# 0151_DC_JACK_RTC_COIN.net
KiCad netlist of a schematic drawn in Altium Designer
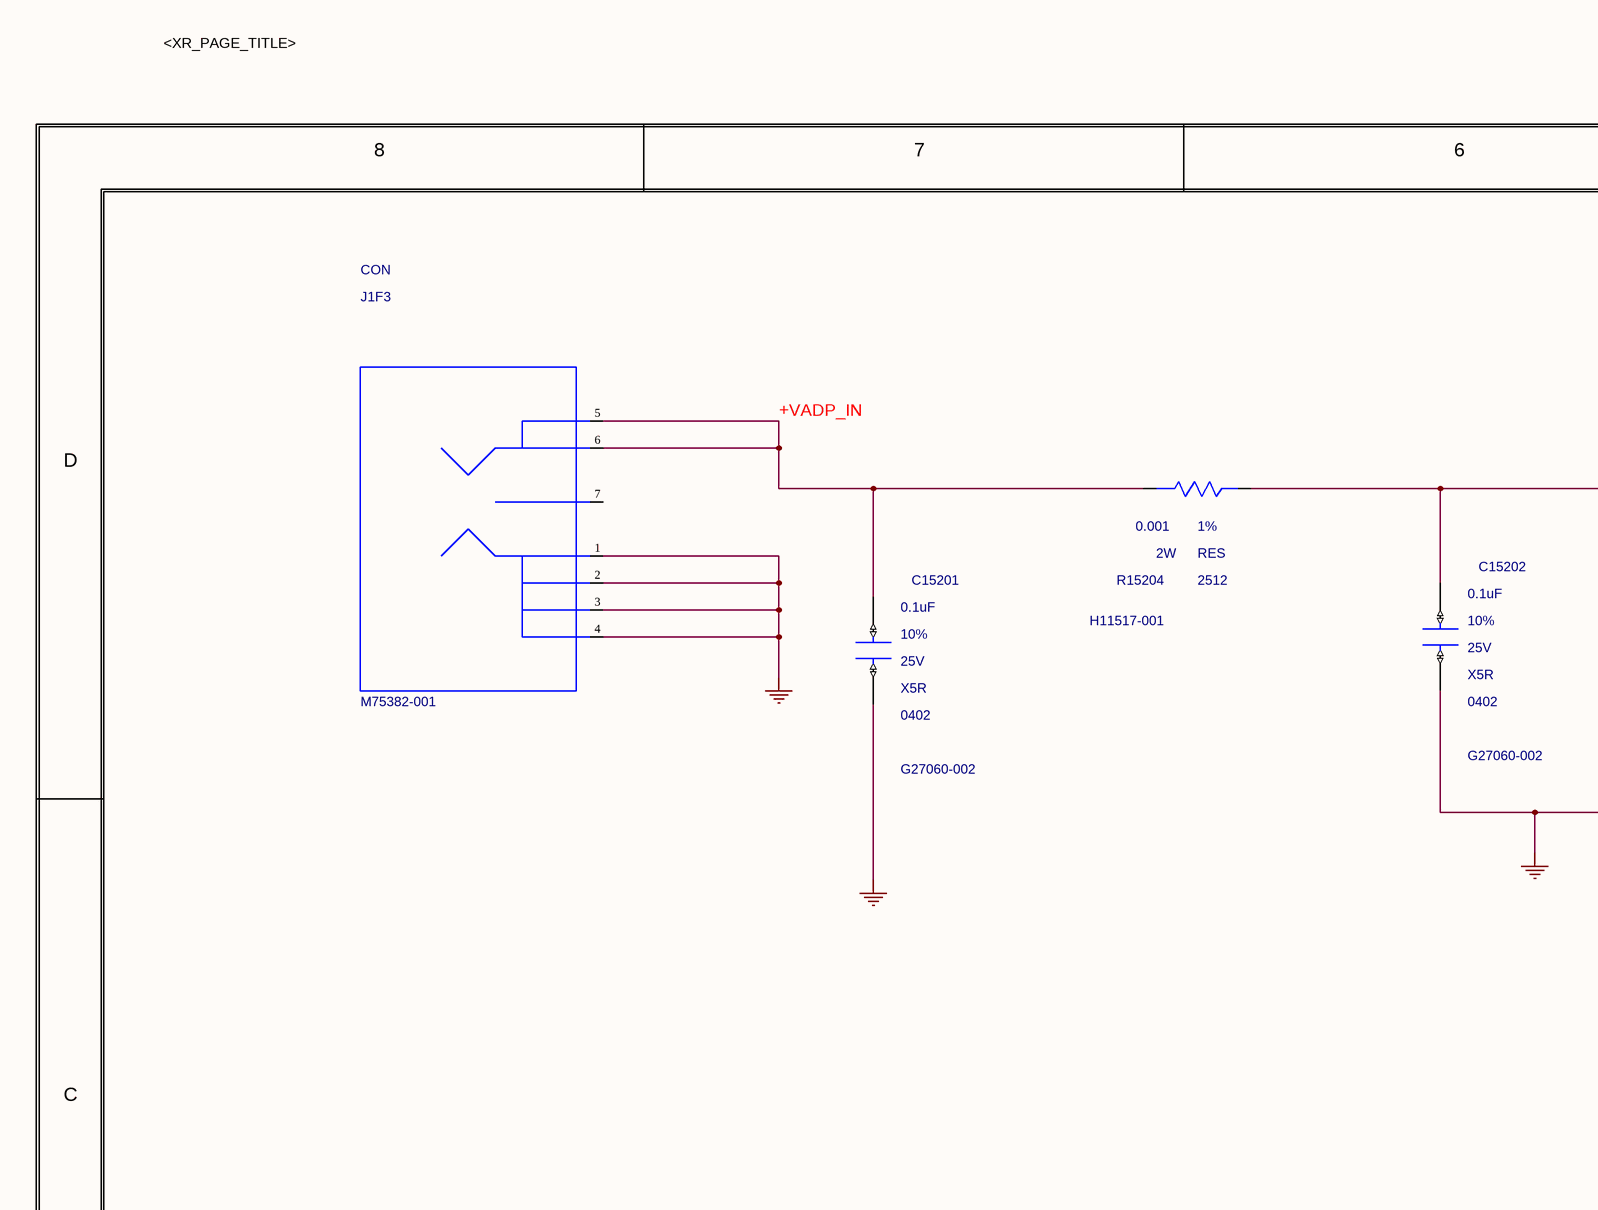
[diagram p0: 0151_DC JACK & RTC COIN.SchDoc, top left]
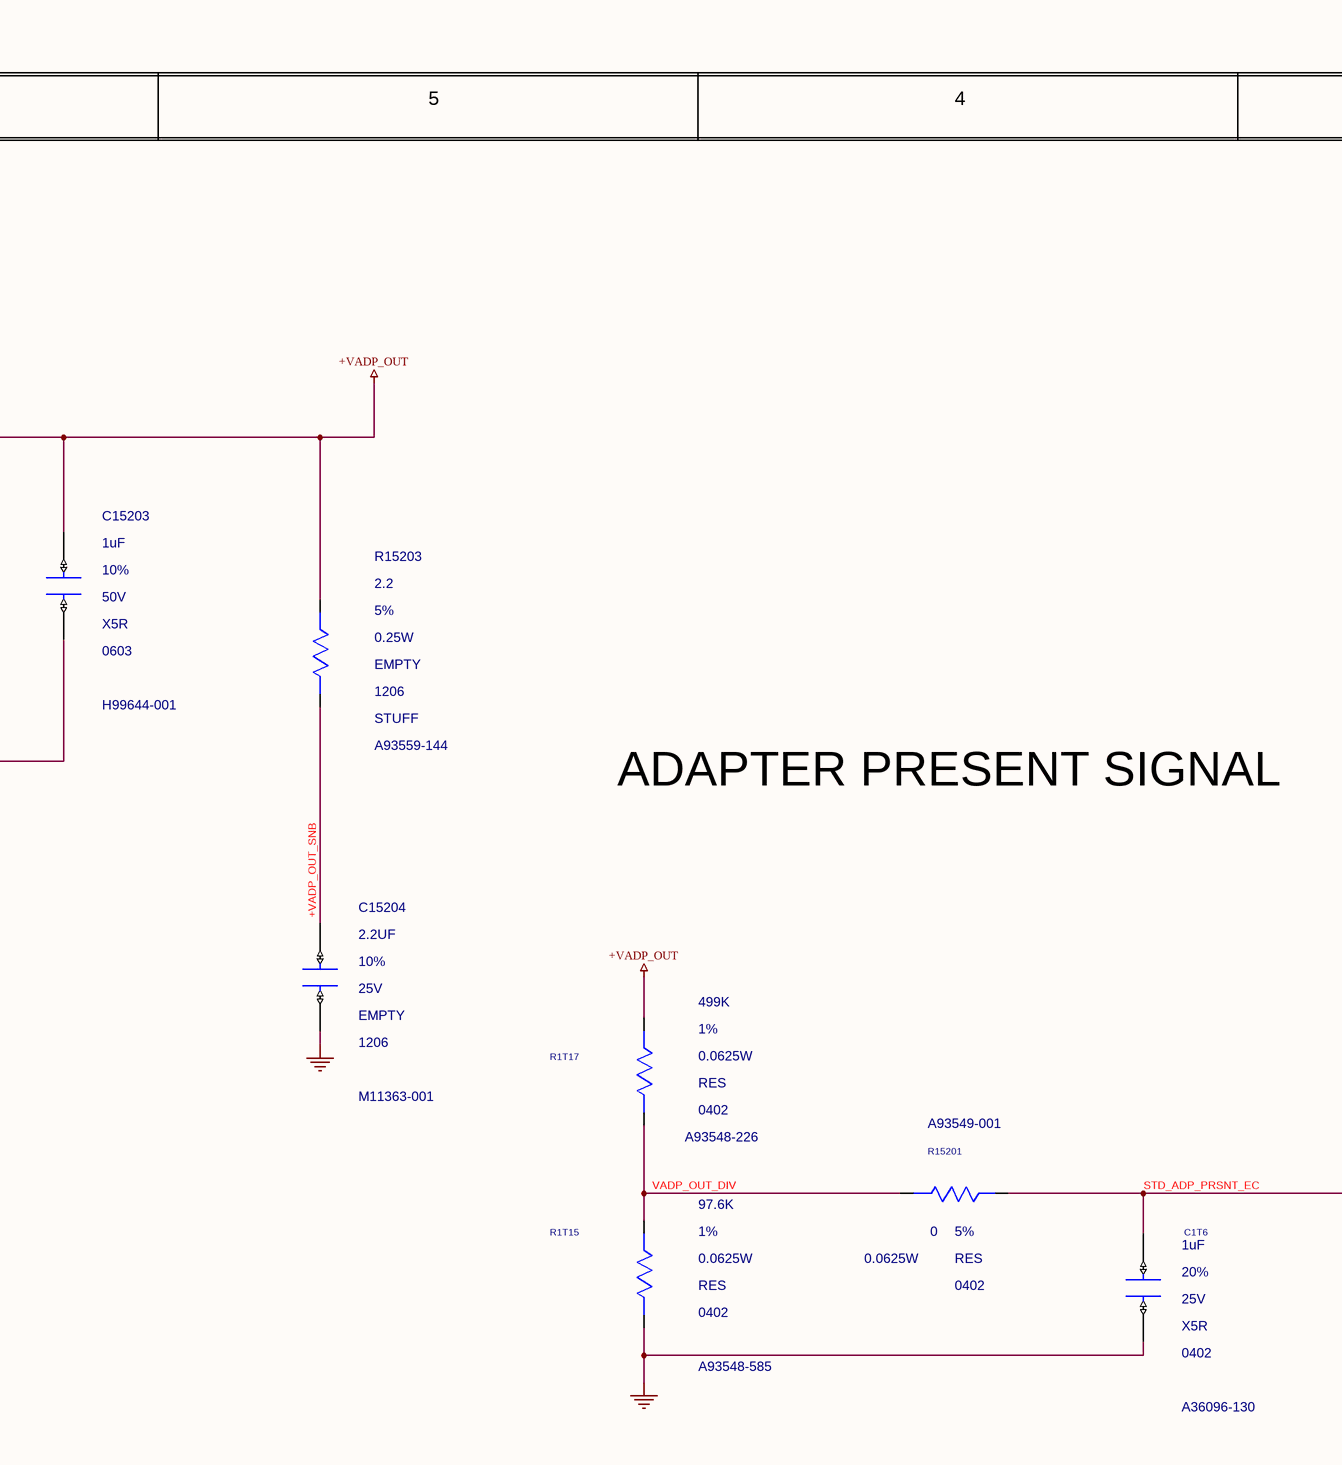
[diagram p1: 0151_DC JACK & RTC COIN.SchDoc, top middle]
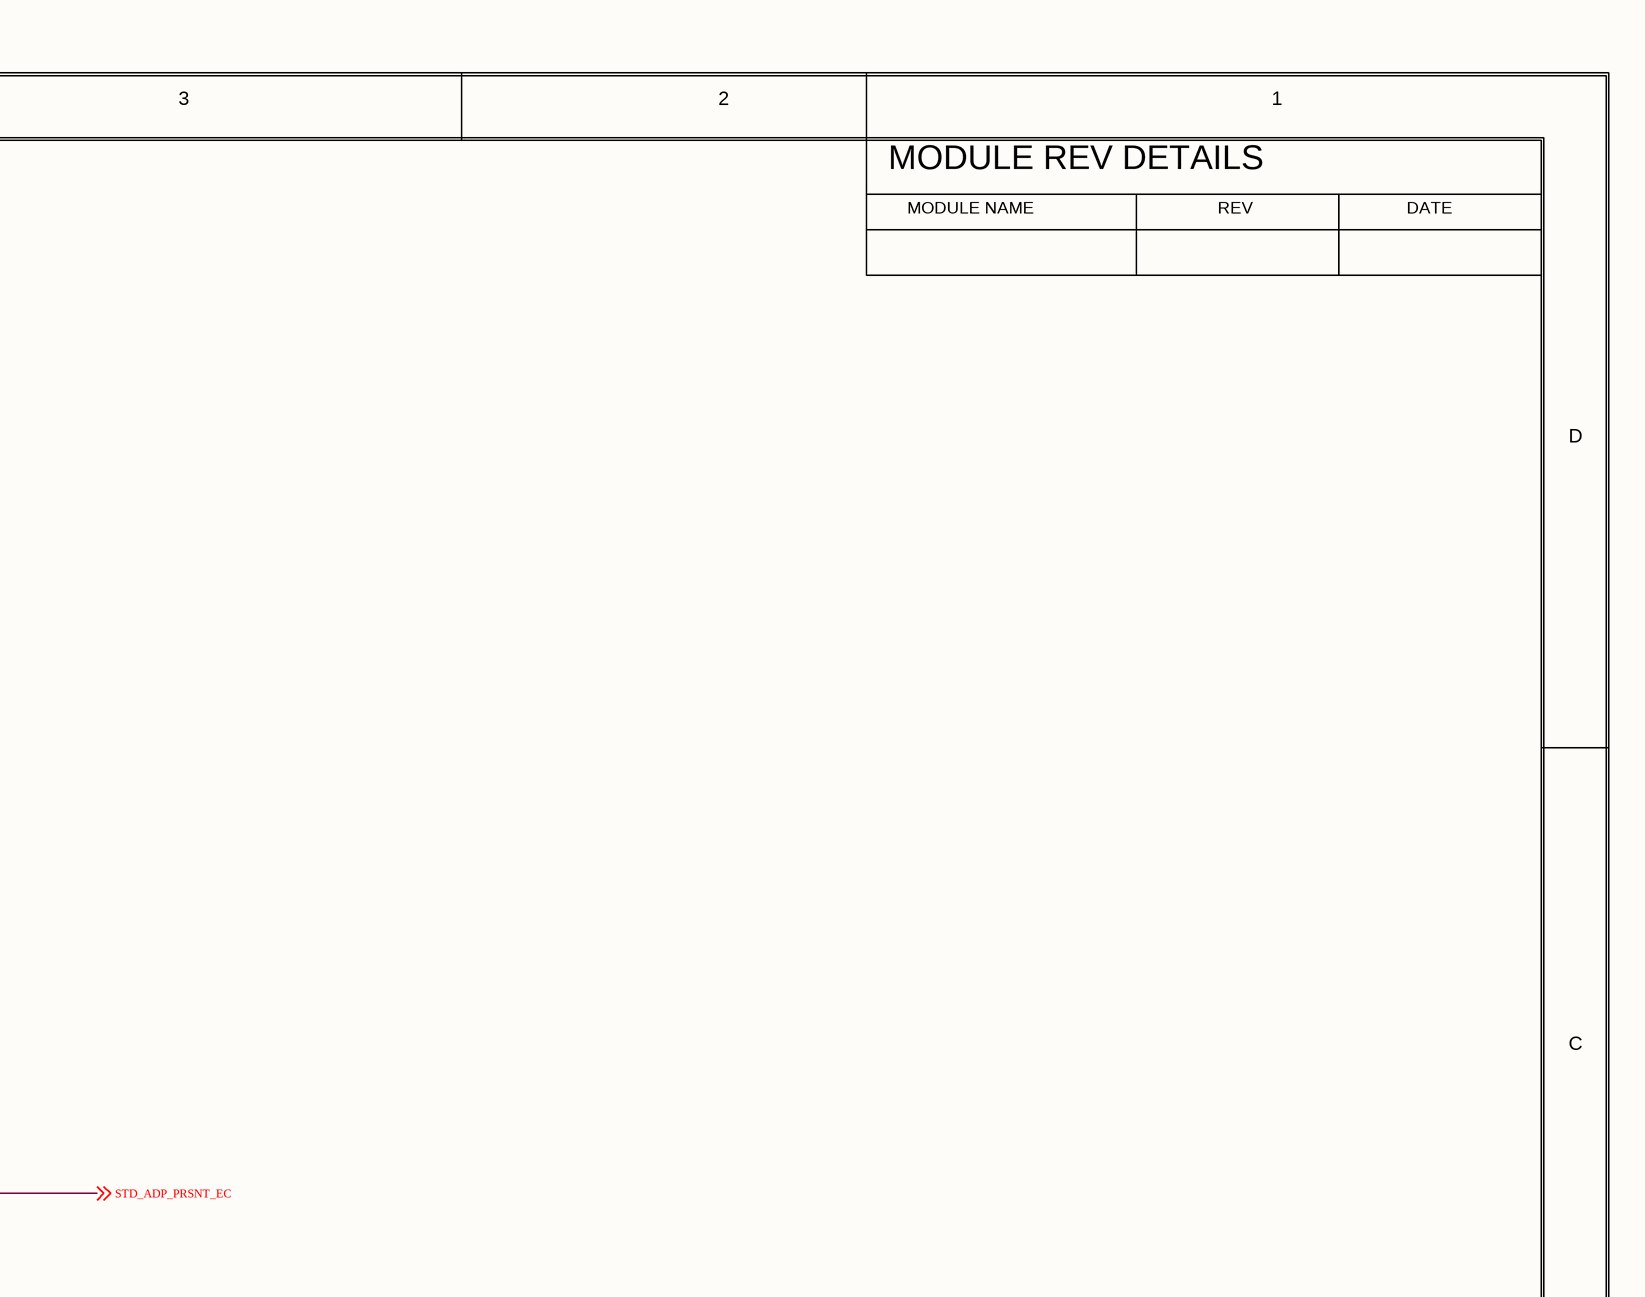
[diagram p2: 0151_DC JACK & RTC COIN.SchDoc, top right]
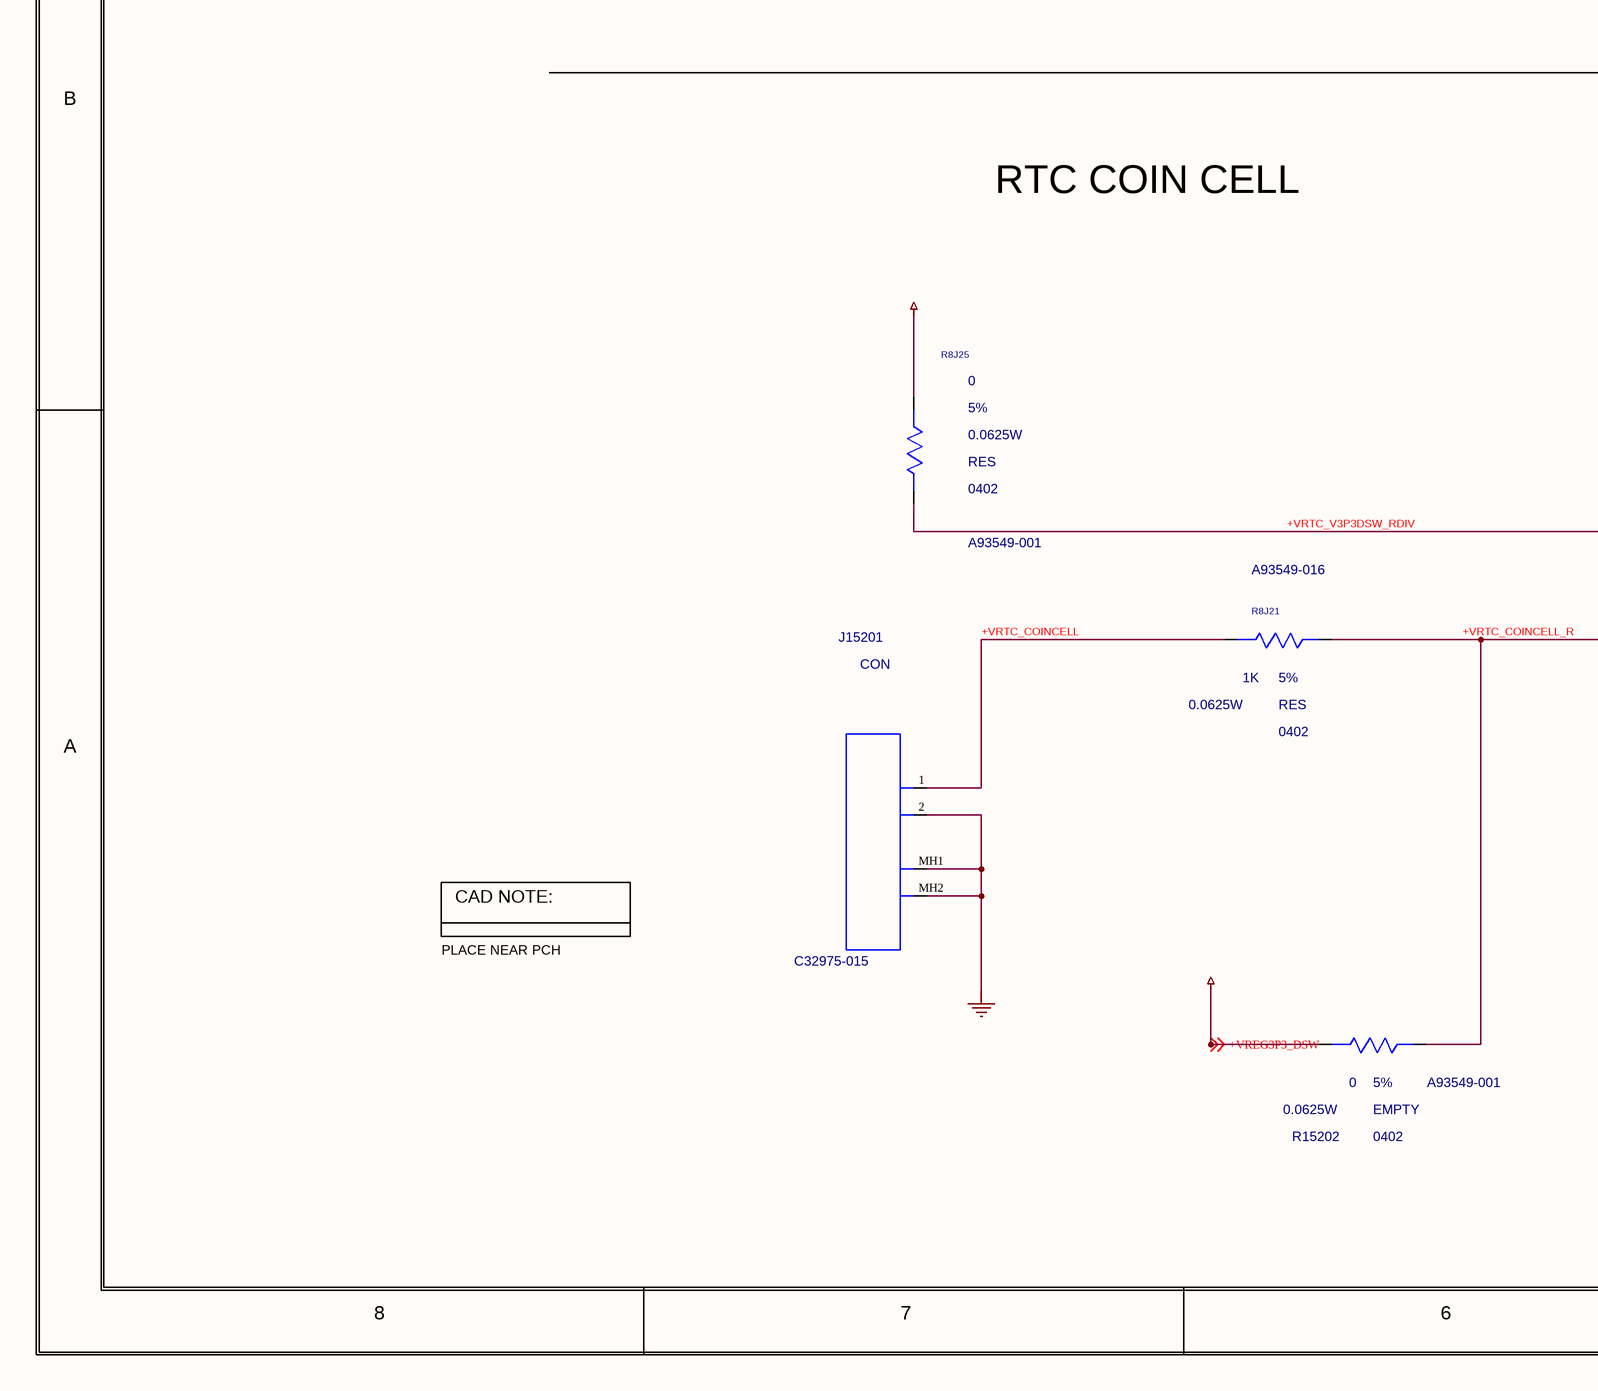
[diagram p3: 0151_DC JACK & RTC COIN.SchDoc, bottom left]
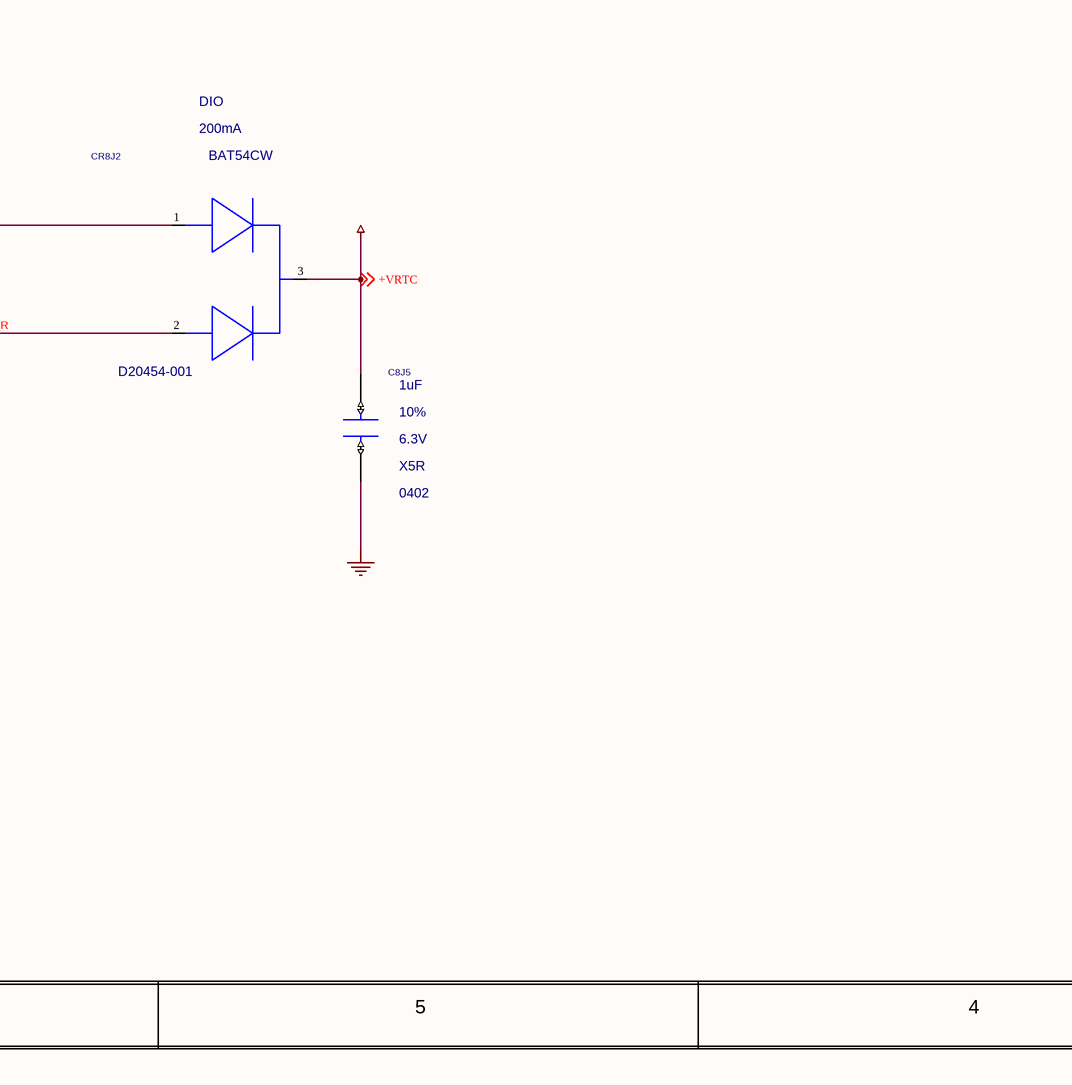
[diagram p4: 0151_DC JACK & RTC COIN.SchDoc, bottom middle]
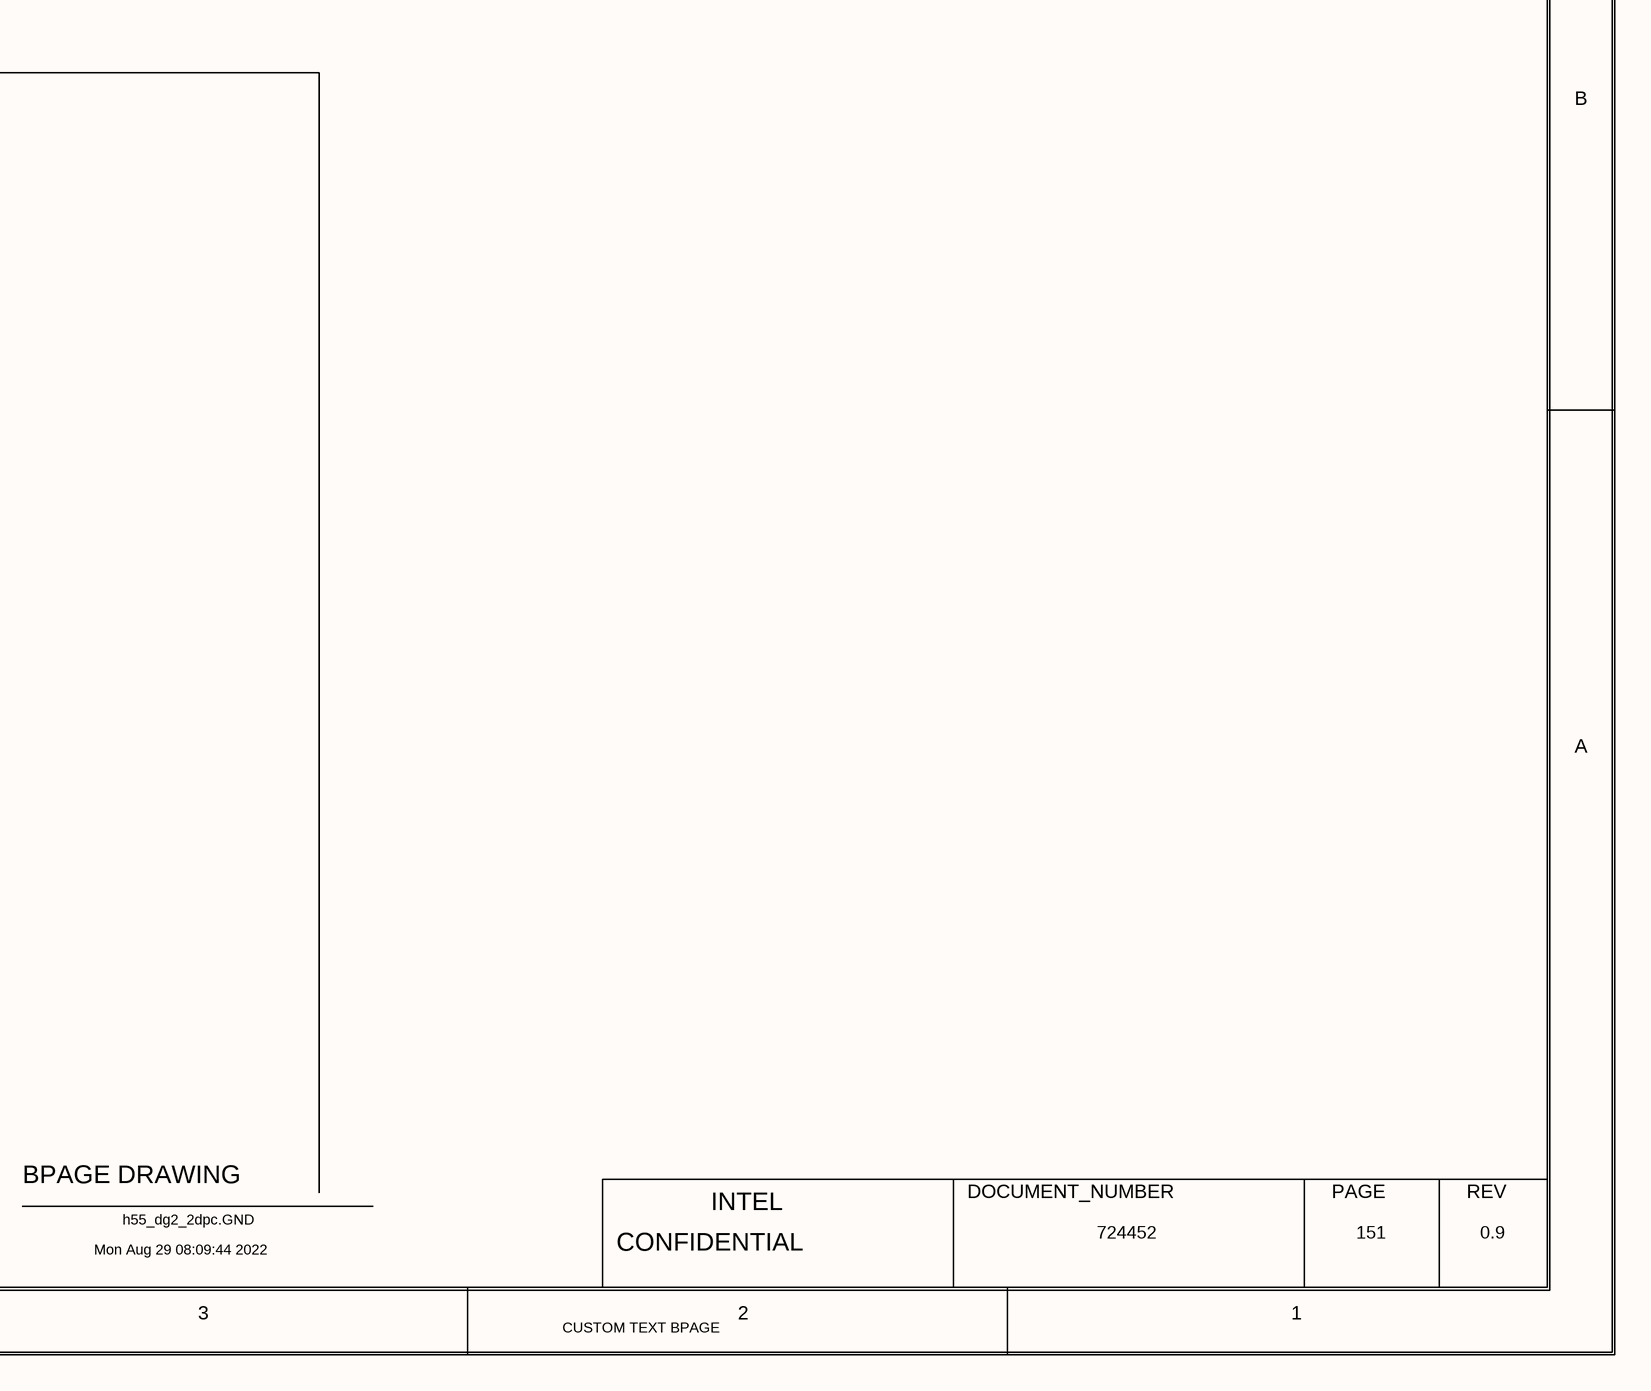
[diagram p5: 0151_DC JACK & RTC COIN.SchDoc, bottom right]

(export (version "E")
  (design (tool "Eeschema 10.0.6"))
  (components
    (comp (ref "C1T6")
      (value "1uF")
      (footprint "CTK0_SM0402_1050X550_MA")
      (fields
        (field (name "MATERIAL") "X5R")
        (field (name "PACK_TYPE") "0402")
        (field (name "PART_NUMBER") "A36096-130")
        (field (name "TOLERANCE") "20%")
        (field (name "VOLTAGE") "25V")
      )
      (libsource (lib "*") (part "C_CAP"))
    )
    (comp (ref "C8J5")
      (value "1uF")
      (footprint "CTK2_SM0402_1050X550_MA")
      (fields
        (field (name "MATERIAL") "X5R")
        (field (name "PACK_TYPE") "0402")
        (field (name "PART_NUMBER") "A36096-027")
        (field (name "TOLERANCE") "10%")
        (field (name "VOLTAGE") "6.3V")
      )
      (libsource (lib "*") (part "C_CAP"))
    )
    (comp (ref "C15201")
      (value "0.1uF")
      (footprint "CTK2_SM0402_1050X550_MA")
      (fields
        (field (name "MATERIAL") "X5R")
        (field (name "PACK_TYPE") "0402")
        (field (name "PART_NUMBER") "G27060-002")
        (field (name "TOLERANCE") "10%")
        (field (name "VOLTAGE") "25V")
      )
      (libsource (lib "*") (part "C_CAP"))
    )
    (comp (ref "C15202")
      (value "0.1uF")
      (footprint "CTK2_SM0402_1050X550_MA")
      (fields
        (field (name "MATERIAL") "X5R")
        (field (name "PACK_TYPE") "0402")
        (field (name "PART_NUMBER") "G27060-002")
        (field (name "TOLERANCE") "10%")
        (field (name "VOLTAGE") "25V")
      )
      (libsource (lib "*") (part "C_CAP"))
    )
    (comp (ref "C15203")
      (value "1uF")
      (footprint "CTK0_SM0603_1750X950_MA")
      (fields
        (field (name "MATERIAL") "X5R")
        (field (name "PACK_TYPE") "0603")
        (field (name "PART_NUMBER") "H99644-001")
        (field (name "TOLERANCE") "10%")
        (field (name "VOLTAGE") "50V")
      )
      (libsource (lib "*") (part "C_CAP"))
    )
    (comp (ref "C15204")
      (value "2.2UF")
      (footprint "CTK2_SM1206_3400X1800_MB")
      (fields
        (field (name "MATERIAL") "EMPTY")
        (field (name "PACK_TYPE") "1206")
        (field (name "PART_NUMBER") "M11363-001")
        (field (name "TOLERANCE") "10%")
        (field (name "VOLTAGE") "25V")
      )
      (libsource (lib "*") (part "C_CAP"))
    )
    (comp (ref "CR8J2")
      (value "BAT54CW")
      (footprint "CTK2_SOT323_1350X2200_650_MB")
      (fields
        (field (name "CURRENT") "200mA")
        (field (name "MATERIAL") "DIO")
        (field (name "PART_NUMBER") "D20454-001")
      )
      (libsource (lib "*") (part "C_BAT54C"))
    )
    (comp (ref "J1F3")
      (value "C_PWR_JACK_7P")
      (footprint "CPWR_JACK_MIDJR_7P_1530_MA_PIP_VR")
      (fields (field (name "MATERIAL") "CON") (field (name "PART_NUMBER") "M75382-001"))
      (libsource (lib "*") (part "C_PWR_JACK_7P"))
    )
    (comp (ref "J15201")
      (value "C_B2B_1X2_2EM")
      (footprint "CTK0_B2B_SPR_1X2_2EM_1250_MA_VR")
      (fields (field (name "MATERIAL") "CON") (field (name "PART_NUMBER") "C32975-015"))
      (libsource (lib "*") (part "C_B2B_1X2_2EM"))
    )
    (comp (ref "R1T15")
      (value "97.6K")
      (footprint "CTK0_SM0402_1100X550_MA")
      (fields
        (field (name "MATERIAL") "RES")
        (field (name "PACK_TYPE") "0402")
        (field (name "PART_NUMBER") "A93548-585")
        (field (name "TOLERANCE") "1%")
        (field (name "WATTAGE") "0.0625W")
      )
      (libsource (lib "*") (part "C_RES"))
    )
    (comp (ref "R1T17")
      (value "499K")
      (footprint "CTK0_SM0402_1100X550_MA")
      (fields
        (field (name "MATERIAL") "RES")
        (field (name "PACK_TYPE") "0402")
        (field (name "PART_NUMBER") "A93548-226")
        (field (name "TOLERANCE") "1%")
        (field (name "WATTAGE") "0.0625W")
      )
      (libsource (lib "*") (part "C_RES"))
    )
    (comp (ref "R8J21")
      (value "1K")
      (footprint "CTK2_SM0402_1050X550_MA")
      (fields
        (field (name "MATERIAL") "RES")
        (field (name "PACK_TYPE") "0402")
        (field (name "PART_NUMBER") "A93549-016")
        (field (name "TOLERANCE") "5%")
        (field (name "WATTAGE") "0.0625W")
      )
      (libsource (lib "*") (part "C_RES#1"))
    )
    (comp (ref "R8J25")
      (value "0")
      (footprint "CTK0_SM0402_1100X550_MA")
      (fields
        (field (name "MATERIAL") "RES")
        (field (name "PACK_TYPE") "0402")
        (field (name "PART_NUMBER") "A93549-001")
        (field (name "TOLERANCE") "5%")
        (field (name "WATTAGE") "0.0625W")
      )
      (libsource (lib "*") (part "C_RES"))
    )
    (comp (ref "R15201")
      (value "0")
      (footprint "CTK0_SM0402_1100X550_MA")
      (fields
        (field (name "MATERIAL") "RES")
        (field (name "PACK_TYPE") "0402")
        (field (name "PART_NUMBER") "A93549-001")
        (field (name "TOLERANCE") "5%")
        (field (name "WATTAGE") "0.0625W")
      )
      (libsource (lib "*") (part "C_RES#1"))
    )
    (comp (ref "R15202")
      (value "0")
      (footprint "CTK0_SM0402_1100X550_MA")
      (fields
        (field (name "MATERIAL") "EMPTY")
        (field (name "PACK_TYPE") "0402")
        (field (name "PART_NUMBER") "A93549-001")
        (field (name "TOLERANCE") "5%")
        (field (name "WATTAGE") "0.0625W")
      )
      (libsource (lib "*") (part "C_RES#1"))
    )
    (comp (ref "R15203")
      (value "2.2")
      (footprint "TK0_SM1206_3400X1800_ML")
      (fields
        (field (name "BOM_USE") "STUFF")
        (field (name "MATERIAL") "EMPTY")
        (field (name "PACK_TYPE") "1206")
        (field (name "PART_NUMBER") "A93559-144")
        (field (name "TOLERANCE") "5%")
        (field (name "WATTAGE") "0.25W")
      )
      (libsource (lib "*") (part "RES_2"))
    )
    (comp (ref "R15204")
      (value "0.001")
      (footprint "CTK2_SM2512_6604X3434_MA")
      (fields
        (field (name "MATERIAL") "RES")
        (field (name "PACK_TYPE") "2512")
        (field (name "PART_NUMBER") "H11517-001")
        (field (name "TOLERANCE") "1%")
        (field (name "WATTAGE") "2W")
      )
      (libsource (lib "*") (part "C_RES#1"))
    )
  )
  (nets
    (net (code "1") (name "+V3P3DSW") (class "Default")
      (node (ref "R8J25") (pin "1") (pinfunction "A_1") (pintype "bidirectional"))
    )
    (net (code "2") (name "+VADP_OUT") (class "Default")
      (node (ref "C15202") (pin "1") (pinfunction "A_1") (pintype "bidirectional"))
      (node (ref "C15203") (pin "1") (pinfunction "A_1") (pintype "bidirectional"))
      (node (ref "R15203") (pin "1") (pinfunction "A_1") (pintype "bidirectional"))
      (node (ref "R15204") (pin "2") (pinfunction "B_2") (pintype "bidirectional"))
      (node (ref "R1T17") (pin "1") (pinfunction "A_1") (pintype "bidirectional"))
    )
    (net (code "3") (name "+VREG3P3_DSW") (class "Default")
      (node (ref "R15202") (pin "1") (pinfunction "A_1") (pintype "bidirectional"))
    )
    (net (code "4") (name "+VRTC") (class "Default")
      (node (ref "C8J5") (pin "1") (pinfunction "A_1") (pintype "bidirectional"))
      (node (ref "CR8J2") (pin "3") (pinfunction "C_3") (pintype "bidirectional"))
    )
    (net (code "5") (name "/+VADP_IN") (class "Default")
      (node (ref "C15201") (pin "1") (pinfunction "A_1") (pintype "bidirectional"))
      (node (ref "J1F3") (pin "5") (pinfunction "SPRING_P_1_5") (pintype "bidirectional"))
      (node (ref "J1F3") (pin "6") (pinfunction "SPRING_P_2_6") (pintype "bidirectional"))
      (node (ref "R15204") (pin "1") (pinfunction "A_1") (pintype "bidirectional"))
    )
    (net (code "6") (name "/+VADP_OUT_SNB") (class "Default")
      (node (ref "C15204") (pin "1") (pinfunction "A_1") (pintype "bidirectional"))
      (node (ref "R15203") (pin "2") (pinfunction "B_2") (pintype "bidirectional"))
    )
    (net (code "7") (name "/+VRTC_COINCELL") (class "Default")
      (node (ref "J15201") (pin "1") (pinfunction "IO1_1") (pintype "bidirectional"))
      (node (ref "R8J21") (pin "1") (pinfunction "A_1") (pintype "bidirectional"))
    )
    (net (code "8") (name "/+VRTC_COINCELL_R") (class "Default")
      (node (ref "CR8J2") (pin "2") (pinfunction "A2_2") (pintype "bidirectional"))
      (node (ref "R15202") (pin "2") (pinfunction "B_2") (pintype "bidirectional"))
      (node (ref "R8J21") (pin "2") (pinfunction "B_2") (pintype "bidirectional"))
    )
    (net (code "9") (name "/+VRTC_V3P3DSW_RDIV") (class "Default")
      (node (ref "CR8J2") (pin "1") (pinfunction "A1_1") (pintype "bidirectional"))
      (node (ref "R8J25") (pin "2") (pinfunction "B_2") (pintype "bidirectional"))
    )
    (net (code "10") (name "/VADP_OUT_DIV") (class "Default")
      (node (ref "R15201") (pin "1") (pinfunction "A_1") (pintype "bidirectional"))
      (node (ref "R1T15") (pin "1") (pinfunction "A_1") (pintype "bidirectional"))
      (node (ref "R1T17") (pin "2") (pinfunction "B_2") (pintype "bidirectional"))
    )
    (net (code "11") (name "GND") (class "Default")
      (node (ref "C15201") (pin "2") (pinfunction "B_2") (pintype "bidirectional"))
      (node (ref "C15202") (pin "2") (pinfunction "B_2") (pintype "bidirectional"))
      (node (ref "C15203") (pin "2") (pinfunction "B_2") (pintype "bidirectional"))
      (node (ref "C15204") (pin "2") (pinfunction "B_2") (pintype "bidirectional"))
      (node (ref "C1T6") (pin "2") (pinfunction "B_2") (pintype "bidirectional"))
      (node (ref "C8J5") (pin "2") (pinfunction "B_2") (pintype "bidirectional"))
      (node (ref "J15201") (pin "2") (pinfunction "IO2_2") (pintype "bidirectional"))
      (node (ref "J15201") (pin "MH1") (pinfunction "MH1_MH1") (pintype "bidirectional"))
      (node (ref "J15201") (pin "MH2") (pinfunction "MH2_MH2") (pintype "bidirectional"))
      (node (ref "J1F3") (pin "1") (pinfunction "SHELL_M_1_1") (pintype "bidirectional"))
      (node (ref "J1F3") (pin "2") (pinfunction "SHELL_M_2_2") (pintype "bidirectional"))
      (node (ref "J1F3") (pin "3") (pinfunction "SHELL_M_3_3") (pintype "bidirectional"))
      (node (ref "J1F3") (pin "4") (pinfunction "SHELL_M_4_4") (pintype "bidirectional"))
      (node (ref "R1T15") (pin "2") (pinfunction "B_2") (pintype "bidirectional"))
    )
    (net (code "12") (name "STD_ADP_PRSNT_EC") (class "Default")
      (node (ref "C1T6") (pin "1") (pinfunction "A_1") (pintype "bidirectional"))
      (node (ref "R15201") (pin "2") (pinfunction "B_2") (pintype "bidirectional"))
    )
    (net (code "13") (name "unconnected-(J1F3-ID-Pad7)") (class "Default")
      (node (ref "J1F3") (pin "7") (pinfunction "ID_7") (pintype "bidirectional"))
    )
  )
)
